# manette.net
KiCad netlist of a schematic drawn in Altium Designer
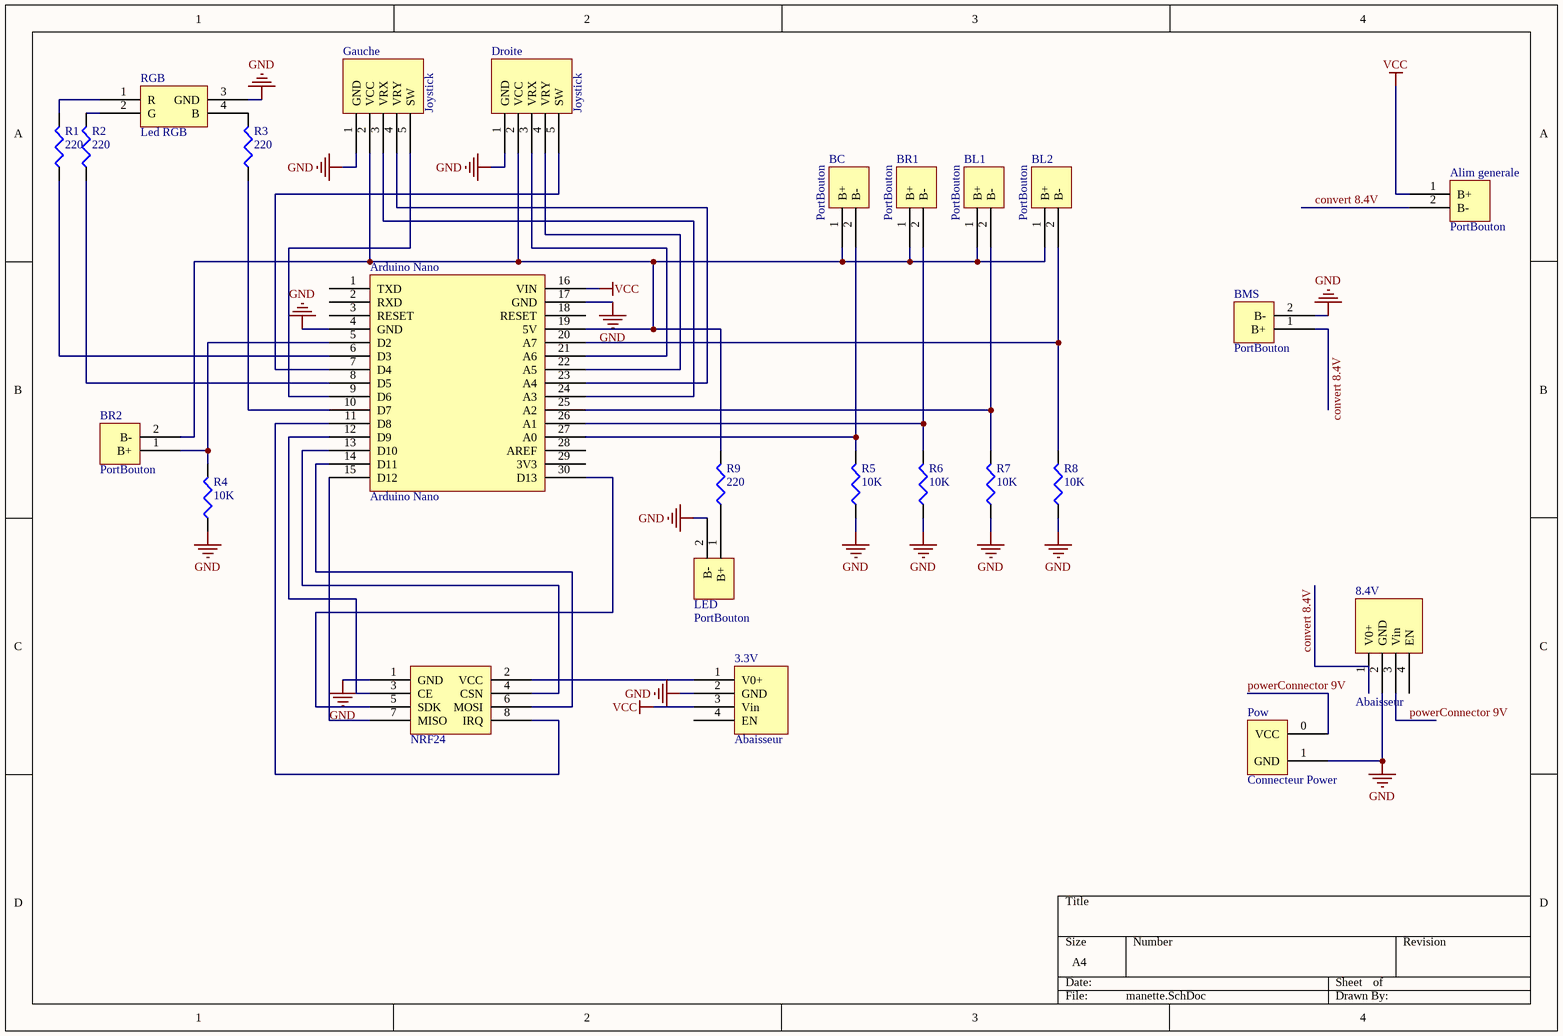
[diagram p0: manette.SchDoc]

(export (version "E")
  (design (tool "Eeschema 10.0.6"))
  (components
    (comp (ref "3.3V")
      (value "Abaisseur")
      (footprint "AbaisseurTension")
      (libsource (lib "") (part "Abaisseur_1"))
    )
    (comp (ref "8.4V")
      (value "Abaisseur")
      (footprint "AbaisseurTension")
      (libsource (lib "Library") (part "Abaisseur"))
    )
    (comp (ref "Alim generale")
      (value "PortBouton")
      (footprint "PortBouton")
      (libsource (lib "") (part "PortBouton_3"))
    )
    (comp (ref "Arduino Nano")
      (value "Arduino Nano")
      (footprint "Arduino Nano")
      (libsource (lib "Library") (part "Arduino Nano"))
    )
    (comp (ref "BC")
      (value "PortBouton")
      (footprint "PortBouton")
      (libsource (lib "Library") (part "PortBouton"))
    )
    (comp (ref "BL1")
      (value "PortBouton")
      (footprint "PortBouton")
      (libsource (lib "Library") (part "PortBouton"))
    )
    (comp (ref "BL2")
      (value "PortBouton")
      (footprint "PortBouton")
      (libsource (lib "Library") (part "PortBouton"))
    )
    (comp (ref "BMS")
      (value "PortBouton")
      (footprint "PortBouton")
      (libsource (lib "") (part "PortBouton_2"))
    )
    (comp (ref "BR1")
      (value "PortBouton")
      (footprint "PortBouton")
      (libsource (lib "Library") (part "PortBouton"))
    )
    (comp (ref "BR2")
      (value "PortBouton")
      (footprint "PortBouton")
      (libsource (lib "") (part "PortBouton_2"))
    )
    (comp (ref "Droite")
      (value "Joystick")
      (footprint "Joystick")
      (libsource (lib "Library") (part "Joystick"))
    )
    (comp (ref "Gauche")
      (value "Joystick")
      (footprint "Joystick")
      (libsource (lib "Library") (part "Joystick"))
    )
    (comp (ref "LED")
      (value "PortBouton")
      (footprint "PortBouton")
      (libsource (lib "") (part "PortBouton_1"))
    )
    (comp (ref "NRF24") (value "NRF24") (footprint "NRF24") (libsource (lib "Library") (part "NRF24")))
    (comp (ref "Pow")
      (value "Connecteur Power")
      (footprint "Connecteur Power")
      (libsource (lib "Connectorpower") (part "Connecteur Power"))
    )
    (comp (ref "R1")
      (value "220")
      (footprint "0805")
      (description "resistance")
      (fields (field (name "Comment") "RES"))
      (libsource (lib "ISEN_basics") (part "RES"))
    )
    (comp (ref "R2")
      (value "220")
      (footprint "0805")
      (description "resistance")
      (fields (field (name "Comment") "RES"))
      (libsource (lib "ISEN_basics") (part "RES"))
    )
    (comp (ref "R3")
      (value "220")
      (footprint "0805")
      (description "resistance")
      (fields (field (name "Comment") "RES"))
      (libsource (lib "ISEN_basics") (part "RES"))
    )
    (comp (ref "R4")
      (value "10K")
      (footprint "0805")
      (description "resistance")
      (fields (field (name "Comment") "RES"))
      (libsource (lib "ISEN_basics") (part "RES"))
    )
    (comp (ref "R5")
      (value "10K")
      (footprint "0805")
      (description "resistance")
      (fields (field (name "Comment") "RES"))
      (libsource (lib "ISEN_basics") (part "RES"))
    )
    (comp (ref "R6")
      (value "10K")
      (footprint "0805")
      (description "resistance")
      (fields (field (name "Comment") "RES"))
      (libsource (lib "ISEN_basics") (part "RES"))
    )
    (comp (ref "R7")
      (value "10K")
      (footprint "0805")
      (description "resistance")
      (fields (field (name "Comment") "RES"))
      (libsource (lib "ISEN_basics") (part "RES"))
    )
    (comp (ref "R8")
      (value "10K")
      (footprint "0805")
      (description "resistance")
      (fields (field (name "Comment") "RES"))
      (libsource (lib "ISEN_basics") (part "RES"))
    )
    (comp (ref "R9")
      (value "220")
      (footprint "0805")
      (description "resistance")
      (fields (field (name "Comment") "RES"))
      (libsource (lib "ISEN_basics") (part "RES"))
    )
    (comp (ref "RGB") (value "Led RGB") (footprint "Led RGB") (libsource (lib "Library") (part "Led RGB")))
  )
  (nets
    (net (code "1") (name "/convert 8.4V") (class "Default")
      (node (ref "8.4V") (pin "1") (pinfunction "V0+_1") (pintype "passive"))
      (node (ref "Alim generale") (pin "2") (pinfunction "B-_2") (pintype "passive"))
      (node (ref "BMS") (pin "1") (pinfunction "B+_1") (pintype "passive"))
    )
    (net (code "2") (name "/powerConnector 9V") (class "Default")
      (node (ref "8.4V") (pin "3") (pinfunction "Vin_3") (pintype "passive"))
      (node (ref "Pow") (pin "0") (pinfunction "VCC_0") (pintype "passive"))
    )
    (net (code "3") (name "GND") (class "Default")
      (node (ref "3.3V") (pin "2") (pinfunction "GND_2") (pintype "passive"))
      (node (ref "8.4V") (pin "2") (pinfunction "GND_2") (pintype "passive"))
      (node (ref "Arduino Nano") (pin "17") (pinfunction "GND_17") (pintype "passive"))
      (node (ref "Arduino Nano") (pin "4") (pinfunction "GND_4") (pintype "passive"))
      (node (ref "BMS") (pin "2") (pinfunction "B-_2") (pintype "passive"))
      (node (ref "Droite") (pin "1") (pinfunction "GND_1") (pintype "passive"))
      (node (ref "Gauche") (pin "1") (pinfunction "GND_1") (pintype "passive"))
      (node (ref "LED") (pin "2") (pinfunction "B-_2") (pintype "passive"))
      (node (ref "NRF24") (pin "1") (pinfunction "GND_1") (pintype "passive"))
      (node (ref "Pow") (pin "1") (pinfunction "GND_1") (pintype "passive"))
      (node (ref "R4") (pin "1") (pintype "passive"))
      (node (ref "R5") (pin "1") (pintype "passive"))
      (node (ref "R6") (pin "1") (pintype "passive"))
      (node (ref "R7") (pin "1") (pintype "passive"))
      (node (ref "R8") (pin "1") (pintype "passive"))
      (node (ref "RGB") (pin "3") (pinfunction "GND_3") (pintype "passive"))
    )
    (net (code "4") (name "Net-(3.3V-V0+)") (class "Default")
      (node (ref "3.3V") (pin "1") (pinfunction "V0+_1") (pintype "passive"))
      (node (ref "NRF24") (pin "2") (pinfunction "VCC_2") (pintype "passive"))
    )
    (net (code "5") (name "Net-(Arduino Nano-5V)") (class "Default")
      (node (ref "Arduino Nano") (pin "19") (pinfunction "5V_19") (pintype "passive"))
      (node (ref "BC") (pin "1") (pinfunction "B+_1") (pintype "passive"))
      (node (ref "BL1") (pin "1") (pinfunction "B+_1") (pintype "passive"))
      (node (ref "BL2") (pin "1") (pinfunction "B+_1") (pintype "passive"))
      (node (ref "BR1") (pin "1") (pinfunction "B+_1") (pintype "passive"))
      (node (ref "BR2") (pin "2") (pinfunction "B-_2") (pintype "passive"))
      (node (ref "Droite") (pin "2") (pinfunction "VCC_2") (pintype "passive"))
      (node (ref "Gauche") (pin "2") (pinfunction "VCC_2") (pintype "passive"))
      (node (ref "R9") (pin "2") (pintype "passive"))
    )
    (net (code "6") (name "Net-(Arduino Nano-A0)") (class "Default")
      (node (ref "Arduino Nano") (pin "27") (pinfunction "A0_27") (pintype "passive"))
      (node (ref "BC") (pin "2") (pinfunction "B-_2") (pintype "passive"))
      (node (ref "R5") (pin "2") (pintype "passive"))
    )
    (net (code "7") (name "Net-(Arduino Nano-A1)") (class "Default")
      (node (ref "Arduino Nano") (pin "26") (pinfunction "A1_26") (pintype "passive"))
      (node (ref "BR1") (pin "2") (pinfunction "B-_2") (pintype "passive"))
      (node (ref "R6") (pin "2") (pintype "passive"))
    )
    (net (code "8") (name "Net-(Arduino Nano-A2)") (class "Default")
      (node (ref "Arduino Nano") (pin "25") (pinfunction "A2_25") (pintype "passive"))
      (node (ref "BL1") (pin "2") (pinfunction "B-_2") (pintype "passive"))
      (node (ref "R7") (pin "2") (pintype "passive"))
    )
    (net (code "9") (name "Net-(Arduino Nano-A3)") (class "Default")
      (node (ref "Arduino Nano") (pin "24") (pinfunction "A3_24") (pintype "passive"))
      (node (ref "Gauche") (pin "3") (pinfunction "VRX_3") (pintype "passive"))
    )
    (net (code "10") (name "Net-(Arduino Nano-A4)") (class "Default")
      (node (ref "Arduino Nano") (pin "23") (pinfunction "A4_23") (pintype "passive"))
      (node (ref "Gauche") (pin "4") (pinfunction "VRY_4") (pintype "passive"))
    )
    (net (code "11") (name "Net-(Arduino Nano-A5)") (class "Default")
      (node (ref "Arduino Nano") (pin "22") (pinfunction "A5_22") (pintype "passive"))
      (node (ref "Droite") (pin "4") (pinfunction "VRY_4") (pintype "passive"))
    )
    (net (code "12") (name "Net-(Arduino Nano-A6)") (class "Default")
      (node (ref "Arduino Nano") (pin "21") (pinfunction "A6_21") (pintype "passive"))
      (node (ref "Droite") (pin "3") (pinfunction "VRX_3") (pintype "passive"))
    )
    (net (code "13") (name "Net-(Arduino Nano-A7)") (class "Default")
      (node (ref "Arduino Nano") (pin "20") (pinfunction "A7_20") (pintype "passive"))
      (node (ref "BL2") (pin "2") (pinfunction "B-_2") (pintype "passive"))
      (node (ref "R8") (pin "2") (pintype "passive"))
    )
    (net (code "14") (name "Net-(Arduino Nano-D2)") (class "Default")
      (node (ref "Arduino Nano") (pin "5") (pinfunction "D2_5") (pintype "passive"))
      (node (ref "BR2") (pin "1") (pinfunction "B+_1") (pintype "passive"))
      (node (ref "R4") (pin "2") (pintype "passive"))
    )
    (net (code "15") (name "Net-(Arduino Nano-D3)") (class "Default")
      (node (ref "Arduino Nano") (pin "6") (pinfunction "D3_6") (pintype "passive"))
      (node (ref "R1") (pin "1") (pintype "passive"))
    )
    (net (code "16") (name "Net-(Arduino Nano-D4)") (class "Default")
      (node (ref "Arduino Nano") (pin "7") (pinfunction "D4_7") (pintype "passive"))
      (node (ref "Droite") (pin "5") (pinfunction "SW_5") (pintype "passive"))
    )
    (net (code "17") (name "Net-(Arduino Nano-D5)") (class "Default")
      (node (ref "Arduino Nano") (pin "8") (pinfunction "D5_8") (pintype "passive"))
      (node (ref "R2") (pin "1") (pintype "passive"))
    )
    (net (code "18") (name "Net-(Arduino Nano-D6)") (class "Default")
      (node (ref "Arduino Nano") (pin "9") (pinfunction "D6_9") (pintype "passive"))
      (node (ref "Gauche") (pin "5") (pinfunction "SW_5") (pintype "passive"))
    )
    (net (code "19") (name "Net-(Arduino Nano-D7)") (class "Default")
      (node (ref "Arduino Nano") (pin "10") (pinfunction "D7_10") (pintype "passive"))
      (node (ref "R3") (pin "1") (pintype "passive"))
    )
    (net (code "20") (name "Net-(Arduino Nano-D8)") (class "Default")
      (node (ref "Arduino Nano") (pin "11") (pinfunction "D8_11") (pintype "passive"))
      (node (ref "NRF24") (pin "8") (pinfunction "IRQ_8") (pintype "passive"))
    )
    (net (code "21") (name "Net-(Arduino Nano-D9)") (class "Default")
      (node (ref "Arduino Nano") (pin "12") (pinfunction "D9_12") (pintype "passive"))
      (node (ref "NRF24") (pin "3") (pinfunction "CE_3") (pintype "passive"))
    )
    (net (code "22") (name "Net-(Arduino Nano-D10)") (class "Default")
      (node (ref "Arduino Nano") (pin "13") (pinfunction "D10_13") (pintype "passive"))
      (node (ref "NRF24") (pin "4") (pinfunction "CSN_4") (pintype "passive"))
    )
    (net (code "23") (name "Net-(Arduino Nano-D11)") (class "Default")
      (node (ref "Arduino Nano") (pin "14") (pinfunction "D11_14") (pintype "passive"))
      (node (ref "NRF24") (pin "6") (pinfunction "MOSI_6") (pintype "passive"))
    )
    (net (code "24") (name "Net-(Arduino Nano-D12)") (class "Default")
      (node (ref "Arduino Nano") (pin "15") (pinfunction "D12_15") (pintype "passive"))
      (node (ref "NRF24") (pin "7") (pinfunction "MISO_7") (pintype "passive"))
    )
    (net (code "25") (name "Net-(Arduino Nano-D13)") (class "Default")
      (node (ref "Arduino Nano") (pin "30") (pinfunction "D13_30") (pintype "passive"))
      (node (ref "NRF24") (pin "5") (pinfunction "SDK_5") (pintype "passive"))
    )
    (net (code "26") (name "Net-(LED-B+)") (class "Default")
      (node (ref "LED") (pin "1") (pinfunction "B+_1") (pintype "passive"))
      (node (ref "R9") (pin "1") (pintype "passive"))
    )
    (net (code "27") (name "Net-(RGB-B)") (class "Default")
      (node (ref "R3") (pin "2") (pintype "passive"))
      (node (ref "RGB") (pin "4") (pinfunction "B_4") (pintype "passive"))
    )
    (net (code "28") (name "Net-(RGB-G)") (class "Default")
      (node (ref "R2") (pin "2") (pintype "passive"))
      (node (ref "RGB") (pin "2") (pinfunction "G_2") (pintype "passive"))
    )
    (net (code "29") (name "Net-(RGB-R)") (class "Default")
      (node (ref "R1") (pin "2") (pintype "passive"))
      (node (ref "RGB") (pin "1") (pinfunction "R_1") (pintype "passive"))
    )
    (net (code "30") (name "VCC") (class "Default")
      (node (ref "3.3V") (pin "3") (pinfunction "Vin_3") (pintype "passive"))
      (node (ref "Alim generale") (pin "1") (pinfunction "B+_1") (pintype "passive"))
      (node (ref "Arduino Nano") (pin "16") (pinfunction "VIN_16") (pintype "passive"))
    )
    (net (code "31") (name "unconnected-(3.3V-EN-Pad4)") (class "Default")
      (node (ref "3.3V") (pin "4") (pinfunction "EN_4") (pintype "passive"))
    )
    (net (code "32") (name "unconnected-(8.4V-EN-Pad4)") (class "Default")
      (node (ref "8.4V") (pin "4") (pinfunction "EN_4") (pintype "passive"))
    )
    (net (code "33") (name "unconnected-(Arduino Nano-3V3-Pad29)") (class "Default")
      (node (ref "Arduino Nano") (pin "29") (pinfunction "3V3_29") (pintype "passive"))
    )
    (net (code "34") (name "unconnected-(Arduino Nano-AREF-Pad28)") (class "Default")
      (node (ref "Arduino Nano") (pin "28") (pinfunction "AREF_28") (pintype "passive"))
    )
    (net (code "35") (name "unconnected-(Arduino Nano-RESET-Pad3)") (class "Default")
      (node (ref "Arduino Nano") (pin "3") (pinfunction "RESET_3") (pintype "passive"))
    )
    (net (code "36") (name "unconnected-(Arduino Nano-RESET-Pad18)") (class "Default")
      (node (ref "Arduino Nano") (pin "18") (pinfunction "RESET_18") (pintype "passive"))
    )
    (net (code "37") (name "unconnected-(Arduino Nano-RXD-Pad2)") (class "Default")
      (node (ref "Arduino Nano") (pin "2") (pinfunction "RXD_2") (pintype "passive"))
    )
    (net (code "38") (name "unconnected-(Arduino Nano-TXD-Pad1)") (class "Default")
      (node (ref "Arduino Nano") (pin "1") (pinfunction "TXD_1") (pintype "passive"))
    )
  )
)
